# Display.net
KiCad netlist of a schematic drawn in Altium Designer
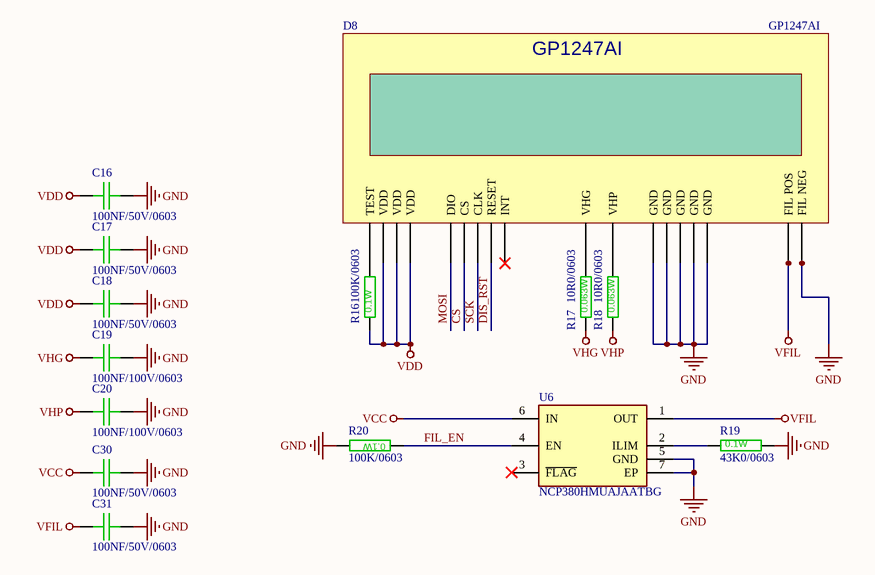
[diagram p0: Display.SchDoc]

(export (version "E")
  (design (tool "Eeschema 10.0.6"))
  (components
    (comp (ref "C16")
      (value "100NF/50V/0603")
      (footprint "0603__R")
      (description "Capacitor, 100nF, 50V, 10%, Ceramic XR7, SMD, 0603")
      (fields
        (field (name "MANUFACTURER") "KEMET")
        (field (name "MANUFACTURER PART NUMBER") "C0603X104K5RACTU")
      )
      (libsource (lib "SCH_SMD_Passive_Capacitor_0603") (part "100NF/50V/0603"))
    )
    (comp (ref "C17")
      (value "100NF/50V/0603")
      (footprint "0603__R")
      (description "Capacitor, 100nF, 50V, 10%, Ceramic XR7, SMD, 0603")
      (fields
        (field (name "MANUFACTURER") "KEMET")
        (field (name "MANUFACTURER PART NUMBER") "C0603X104K5RACTU")
      )
      (libsource (lib "SCH_SMD_Passive_Capacitor_0603") (part "100NF/50V/0603"))
    )
    (comp (ref "C18")
      (value "100NF/50V/0603")
      (footprint "0603__R")
      (description "Capacitor, 100nF, 50V, 10%, Ceramic XR7, SMD, 0603")
      (fields
        (field (name "MANUFACTURER") "KEMET")
        (field (name "MANUFACTURER PART NUMBER") "C0603X104K5RACTU")
      )
      (libsource (lib "SCH_SMD_Passive_Capacitor_0603") (part "100NF/50V/0603"))
    )
    (comp (ref "C19")
      (value "100NF/100V/0603")
      (footprint "0603__R")
      (description "Capacitor, 100nF, 100V, 10%, Ceramic XR7, SMD, 0603")
      (fields
        (field (name "MANUFACTURER") "KEMET")
        (field (name "MANUFACTURER PART NUMBER") "C0603X104K5RACTU")
      )
      (libsource (lib "SCH_SMD_Passive_Capacitor_0603") (part "100NF/50V/0603"))
    )
    (comp (ref "C20")
      (value "100NF/100V/0603")
      (footprint "0603__R")
      (description "Capacitor, 100nF, 100V, 10%, Ceramic XR7, SMD, 0603")
      (fields
        (field (name "MANUFACTURER") "KEMET")
        (field (name "MANUFACTURER PART NUMBER") "C0603X104K5RACTU")
      )
      (libsource (lib "SCH_SMD_Passive_Capacitor_0603") (part "100NF/50V/0603"))
    )
    (comp (ref "C30")
      (value "100NF/50V/0603")
      (footprint "0603__R")
      (description "Capacitor, 100nF, 50V, 10%, Ceramic XR7, SMD, 0603")
      (fields
        (field (name "MANUFACTURER") "KEMET")
        (field (name "MANUFACTURER PART NUMBER") "C0603X104K5RACTU")
      )
      (libsource (lib "SCH_SMD_Passive_Capacitor_0603") (part "100NF/50V/0603"))
    )
    (comp (ref "C31")
      (value "100NF/50V/0603")
      (footprint "0603__R")
      (description "Capacitor, 100nF, 50V, 10%, Ceramic XR7, SMD, 0603")
      (fields
        (field (name "MANUFACTURER") "KEMET")
        (field (name "MANUFACTURER PART NUMBER") "C0603X104K5RACTU")
      )
      (libsource (lib "SCH_SMD_Passive_Capacitor_0603") (part "100NF/50V/0603"))
    )
    (comp (ref "D8")
      (value "GP1247AI")
      (footprint "GP1247AI")
      (description "253*63 Pixels SPI VFD Matrix Display")
      (libsource (lib "GP1247AI") (part "GP1247AI"))
    )
    (comp (ref "R16")
      (value "100K/0603")
      (footprint "0603__R")
      (description "Resistor, 100K, 0.1W, 1%, TK50, Metallschicht, SMD, 0603")
      (libsource (lib "SCH_SMD_Passive_Resistor_0603") (part "100K/0603"))
    )
    (comp (ref "R17")
      (value "10R0/0603")
      (footprint "0603__R")
      (description "Resistor, 10R0, 0.063W, 1%, TK200, Metallschicht, SMD, 0603")
      (fields
        (field (name "MANUFACTURER") "VISHAY")
        (field (name "MANUFACTURER PART NUMBER") "MCT 0603-50 1% P5 10R0")
      )
      (libsource (lib "SCH_SMD_Passive_Resistor_0603") (part "10R0/0603"))
    )
    (comp (ref "R18")
      (value "10R0/0603")
      (footprint "0603__R")
      (description "Resistor, 10R0, 0.063W, 1%, TK200, Metallschicht, SMD, 0603")
      (fields
        (field (name "MANUFACTURER") "VISHAY")
        (field (name "MANUFACTURER PART NUMBER") "MCT 0603-50 1% P5 10R0")
      )
      (libsource (lib "SCH_SMD_Passive_Resistor_0603") (part "10R0/0603"))
    )
    (comp (ref "R19")
      (value "43K0/0603")
      (footprint "0603__R")
      (description "Resistor, 43K0, 0,1 W, 1,0 %, TK50,  Metallschicht, SMD, 0603")
      (libsource (lib "SCH_SMD_Passive_Resistor_0603") (part "43K0/0603"))
    )
    (comp (ref "R20")
      (value "100K/0603")
      (footprint "0603__R")
      (description "Resistor, 100K, 0.1W, 1%, TK50, Metallschicht, SMD, 0603")
      (libsource (lib "SCH_SMD_Passive_Resistor_0603") (part "100K/0603"))
    )
    (comp (ref "U6")
      (value "NCP380HMUAJAATBG")
      (footprint "SON65P200X200X55-7N")
      (fields (field (name "MOUSER PART NUMBER") "863-NCP380HMUAJAATBG"))
      (libsource (lib "GP1247AI") (part "NCP380HMUAJAATBG"))
    )
  )
  (nets
    (net (code "1") (name "/CS") (class "Default")
      (node (ref "D8") (pin "12") (pinfunction "CS_12") (pintype "passive"))
    )
    (net (code "2") (name "/DIS_RST") (class "Default")
      (node (ref "D8") (pin "10") (pinfunction "RESET_10") (pintype "passive"))
    )
    (net (code "3") (name "/FIL_EN") (class "Default")
      (node (ref "R20") (pin "1") (pinfunction "1_1") (pintype "passive"))
      (node (ref "U6") (pin "4") (pinfunction "EN_4") (pintype "passive"))
    )
    (net (code "4") (name "/MOSI") (class "Default")
      (node (ref "D8") (pin "11") (pinfunction "DIO_11") (pintype "passive"))
    )
    (net (code "5") (name "/SCK") (class "Default")
      (node (ref "D8") (pin "13") (pinfunction "CLK_13") (pintype "passive"))
    )
    (net (code "6") (name "GND") (class "Default")
      (node (ref "C16") (pin "1") (pinfunction "1_1") (pintype "passive"))
      (node (ref "C17") (pin "1") (pinfunction "1_1") (pintype "passive"))
      (node (ref "C18") (pin "1") (pinfunction "1_1") (pintype "passive"))
      (node (ref "C19") (pin "1") (pinfunction "1_1") (pintype "passive"))
      (node (ref "C20") (pin "1") (pinfunction "1_1") (pintype "passive"))
      (node (ref "C30") (pin "1") (pinfunction "1_1") (pintype "passive"))
      (node (ref "C31") (pin "1") (pinfunction "1_1") (pintype "passive"))
      (node (ref "D8") (pin "17") (pinfunction "GND_17") (pintype "passive"))
      (node (ref "D8") (pin "19") (pinfunction "GND_19") (pintype "passive"))
      (node (ref "D8") (pin "5") (pinfunction "GND_5") (pintype "passive"))
      (node (ref "D8") (pin "60") (pinfunction "GND_60") (pintype "passive"))
      (node (ref "D8") (pin "61") (pinfunction "GND_61") (pintype "passive"))
      (node (ref "D8") (pin "62") (pinfunction "FIL_NEG_62") (pintype "passive"))
      (node (ref "D8") (pin "63") (pinfunction "FIL_NEG_63") (pintype "passive"))
      (node (ref "D8") (pin "64") (pinfunction "FIL_NEG_64") (pintype "passive"))
      (node (ref "D8") (pin "65") (pinfunction "FIL_NEG_65") (pintype "passive"))
      (node (ref "R19") (pin "2") (pinfunction "2_2") (pintype "passive"))
      (node (ref "R20") (pin "2") (pinfunction "2_2") (pintype "passive"))
      (node (ref "U6") (pin "5") (pinfunction "GND_5") (pintype "passive"))
      (node (ref "U6") (pin "7") (pinfunction "EP_7") (pintype "passive"))
    )
    (net (code "7") (name "Net-(D8-TEST)") (class "Default")
      (node (ref "D8") (pin "9") (pinfunction "TEST_9") (pintype "passive"))
      (node (ref "R16") (pin "2") (pinfunction "2_2") (pintype "passive"))
    )
    (net (code "8") (name "Net-(D8-VHG)") (class "Default")
      (node (ref "D8") (pin "21") (pinfunction "VHG_21") (pintype "passive"))
      (node (ref "R17") (pin "2") (pinfunction "2_2") (pintype "passive"))
    )
    (net (code "9") (name "Net-(D8-VHP)") (class "Default")
      (node (ref "D8") (pin "59") (pinfunction "VHP_59") (pintype "passive"))
      (node (ref "R18") (pin "2") (pinfunction "2_2") (pintype "passive"))
    )
    (net (code "10") (name "Net-(U6-ILIM)") (class "Default")
      (node (ref "R19") (pin "1") (pinfunction "1_1") (pintype "passive"))
      (node (ref "U6") (pin "2") (pinfunction "ILIM_2") (pintype "passive"))
    )
    (net (code "11") (name "VCC") (class "Default")
      (node (ref "C30") (pin "2") (pinfunction "2_2") (pintype "passive"))
      (node (ref "U6") (pin "6") (pinfunction "IN_6") (pintype "passive"))
    )
    (net (code "12") (name "VDD") (class "Default")
      (node (ref "C16") (pin "2") (pinfunction "2_2") (pintype "passive"))
      (node (ref "C17") (pin "2") (pinfunction "2_2") (pintype "passive"))
      (node (ref "C18") (pin "2") (pinfunction "2_2") (pintype "passive"))
      (node (ref "D8") (pin "14") (pinfunction "VDD_14") (pintype "passive"))
      (node (ref "D8") (pin "58") (pinfunction "VDD_58") (pintype "passive"))
      (node (ref "D8") (pin "6") (pinfunction "VDD_6") (pintype "passive"))
      (node (ref "R16") (pin "1") (pinfunction "1_1") (pintype "passive"))
    )
    (net (code "13") (name "VFIL") (class "Default")
      (node (ref "C31") (pin "2") (pinfunction "2_2") (pintype "passive"))
      (node (ref "D8") (pin "1") (pinfunction "FIL_POS_1") (pintype "passive"))
      (node (ref "D8") (pin "2") (pinfunction "FIL_POS_2") (pintype "passive"))
      (node (ref "D8") (pin "3") (pinfunction "FIL_POS_3") (pintype "passive"))
      (node (ref "D8") (pin "4") (pinfunction "FIL_POS_4") (pintype "passive"))
      (node (ref "U6") (pin "1") (pinfunction "OUT_1") (pintype "passive"))
    )
    (net (code "14") (name "VHG") (class "Default")
      (node (ref "C19") (pin "2") (pinfunction "2_2") (pintype "passive"))
      (node (ref "R17") (pin "1") (pinfunction "1_1") (pintype "passive"))
    )
    (net (code "15") (name "VHP") (class "Default")
      (node (ref "C20") (pin "2") (pinfunction "2_2") (pintype "passive"))
      (node (ref "R18") (pin "1") (pinfunction "1_1") (pintype "passive"))
    )
    (net (code "16") (name "unconnected-(D8-INT-Pad15)") (class "Default")
      (node (ref "D8") (pin "15") (pinfunction "INT_15") (pintype "passive+no_connect"))
    )
    (net (code "17") (name "unconnected-(D8-NC-Pad7)") (class "Default")
      (node (ref "D8") (pin "7") (pinfunction "NC_7") (pintype "passive"))
    )
    (net (code "18") (name "unconnected-(D8-NC-Pad8)") (class "Default")
      (node (ref "D8") (pin "8") (pinfunction "NC_8") (pintype "passive"))
    )
    (net (code "19") (name "unconnected-(D8-NC-Pad16)") (class "Default")
      (node (ref "D8") (pin "16") (pinfunction "NC_16") (pintype "passive"))
    )
    (net (code "20") (name "unconnected-(D8-NC-Pad18)") (class "Default")
      (node (ref "D8") (pin "18") (pinfunction "NC_18") (pintype "passive"))
    )
    (net (code "21") (name "unconnected-(D8-NC-Pad20)") (class "Default")
      (node (ref "D8") (pin "20") (pinfunction "NC_20") (pintype "passive"))
    )
    (net (code "22") (name "unconnected-(D8-NC-Pad22)") (class "Default")
      (node (ref "D8") (pin "22") (pinfunction "NC_22") (pintype "passive"))
    )
    (net (code "23") (name "unconnected-(D8-NC-Pad23)") (class "Default")
      (node (ref "D8") (pin "23") (pinfunction "NC_23") (pintype "passive"))
    )
    (net (code "24") (name "unconnected-(D8-NC-Pad24)") (class "Default")
      (node (ref "D8") (pin "24") (pinfunction "NC_24") (pintype "passive"))
    )
    (net (code "25") (name "unconnected-(D8-NC-Pad25)") (class "Default")
      (node (ref "D8") (pin "25") (pinfunction "NC_25") (pintype "passive"))
    )
    (net (code "26") (name "unconnected-(D8-NC-Pad26)") (class "Default")
      (node (ref "D8") (pin "26") (pinfunction "NC_26") (pintype "passive"))
    )
    (net (code "27") (name "unconnected-(D8-NC-Pad27)") (class "Default")
      (node (ref "D8") (pin "27") (pinfunction "NC_27") (pintype "passive"))
    )
    (net (code "28") (name "unconnected-(D8-NC-Pad28)") (class "Default")
      (node (ref "D8") (pin "28") (pinfunction "NC_28") (pintype "passive"))
    )
    (net (code "29") (name "unconnected-(D8-NC-Pad29)") (class "Default")
      (node (ref "D8") (pin "29") (pinfunction "NC_29") (pintype "passive"))
    )
    (net (code "30") (name "unconnected-(D8-NC-Pad30)") (class "Default")
      (node (ref "D8") (pin "30") (pinfunction "NC_30") (pintype "passive"))
    )
    (net (code "31") (name "unconnected-(D8-NC-Pad31)") (class "Default")
      (node (ref "D8") (pin "31") (pinfunction "NC_31") (pintype "passive"))
    )
    (net (code "32") (name "unconnected-(D8-NC-Pad32)") (class "Default")
      (node (ref "D8") (pin "32") (pinfunction "NC_32") (pintype "passive"))
    )
    (net (code "33") (name "unconnected-(D8-NC-Pad33)") (class "Default")
      (node (ref "D8") (pin "33") (pinfunction "NC_33") (pintype "passive"))
    )
    (net (code "34") (name "unconnected-(D8-NC-Pad34)") (class "Default")
      (node (ref "D8") (pin "34") (pinfunction "NC_34") (pintype "passive"))
    )
    (net (code "35") (name "unconnected-(D8-NC-Pad35)") (class "Default")
      (node (ref "D8") (pin "35") (pinfunction "NC_35") (pintype "passive"))
    )
    (net (code "36") (name "unconnected-(D8-NC-Pad36)") (class "Default")
      (node (ref "D8") (pin "36") (pinfunction "NC_36") (pintype "passive"))
    )
    (net (code "37") (name "unconnected-(D8-NC-Pad37)") (class "Default")
      (node (ref "D8") (pin "37") (pinfunction "NC_37") (pintype "passive"))
    )
    (net (code "38") (name "unconnected-(D8-NC-Pad38)") (class "Default")
      (node (ref "D8") (pin "38") (pinfunction "NC_38") (pintype "passive"))
    )
    (net (code "39") (name "unconnected-(D8-NC-Pad39)") (class "Default")
      (node (ref "D8") (pin "39") (pinfunction "NC_39") (pintype "passive"))
    )
    (net (code "40") (name "unconnected-(D8-NC-Pad40)") (class "Default")
      (node (ref "D8") (pin "40") (pinfunction "NC_40") (pintype "passive"))
    )
    (net (code "41") (name "unconnected-(D8-NC-Pad41)") (class "Default")
      (node (ref "D8") (pin "41") (pinfunction "NC_41") (pintype "passive"))
    )
    (net (code "42") (name "unconnected-(D8-NC-Pad42)") (class "Default")
      (node (ref "D8") (pin "42") (pinfunction "NC_42") (pintype "passive"))
    )
    (net (code "43") (name "unconnected-(D8-NC-Pad43)") (class "Default")
      (node (ref "D8") (pin "43") (pinfunction "NC_43") (pintype "passive"))
    )
    (net (code "44") (name "unconnected-(D8-NC-Pad44)") (class "Default")
      (node (ref "D8") (pin "44") (pinfunction "NC_44") (pintype "passive"))
    )
    (net (code "45") (name "unconnected-(D8-NC-Pad45)") (class "Default")
      (node (ref "D8") (pin "45") (pinfunction "NC_45") (pintype "passive"))
    )
    (net (code "46") (name "unconnected-(D8-NC-Pad46)") (class "Default")
      (node (ref "D8") (pin "46") (pinfunction "NC_46") (pintype "passive"))
    )
    (net (code "47") (name "unconnected-(D8-NC-Pad47)") (class "Default")
      (node (ref "D8") (pin "47") (pinfunction "NC_47") (pintype "passive"))
    )
    (net (code "48") (name "unconnected-(D8-NC-Pad48)") (class "Default")
      (node (ref "D8") (pin "48") (pinfunction "NC_48") (pintype "passive"))
    )
    (net (code "49") (name "unconnected-(D8-NC-Pad49)") (class "Default")
      (node (ref "D8") (pin "49") (pinfunction "NC_49") (pintype "passive"))
    )
    (net (code "50") (name "unconnected-(D8-NC-Pad50)") (class "Default")
      (node (ref "D8") (pin "50") (pinfunction "NC_50") (pintype "passive"))
    )
    (net (code "51") (name "unconnected-(D8-NC-Pad51)") (class "Default")
      (node (ref "D8") (pin "51") (pinfunction "NC_51") (pintype "passive"))
    )
    (net (code "52") (name "unconnected-(D8-NC-Pad52)") (class "Default")
      (node (ref "D8") (pin "52") (pinfunction "NC_52") (pintype "passive"))
    )
    (net (code "53") (name "unconnected-(D8-NC-Pad53)") (class "Default")
      (node (ref "D8") (pin "53") (pinfunction "NC_53") (pintype "passive"))
    )
    (net (code "54") (name "unconnected-(D8-NC-Pad54)") (class "Default")
      (node (ref "D8") (pin "54") (pinfunction "NC_54") (pintype "passive"))
    )
    (net (code "55") (name "unconnected-(D8-NC-Pad55)") (class "Default")
      (node (ref "D8") (pin "55") (pinfunction "NC_55") (pintype "passive"))
    )
    (net (code "56") (name "unconnected-(D8-NC-Pad56)") (class "Default")
      (node (ref "D8") (pin "56") (pinfunction "NC_56") (pintype "passive"))
    )
    (net (code "57") (name "unconnected-(D8-NC-Pad57)") (class "Default")
      (node (ref "D8") (pin "57") (pinfunction "NC_57") (pintype "passive"))
    )
    (net (code "58") (name "unconnected-(U6-~{FLAG}-Pad3)") (class "Default")
      (node (ref "U6") (pin "3") (pinfunction "~{FLAG}_3") (pintype "passive+no_connect"))
    )
  )
)
